# CH32V303CBT6-R0.net
KiCad netlist of a schematic drawn in Altium Designer
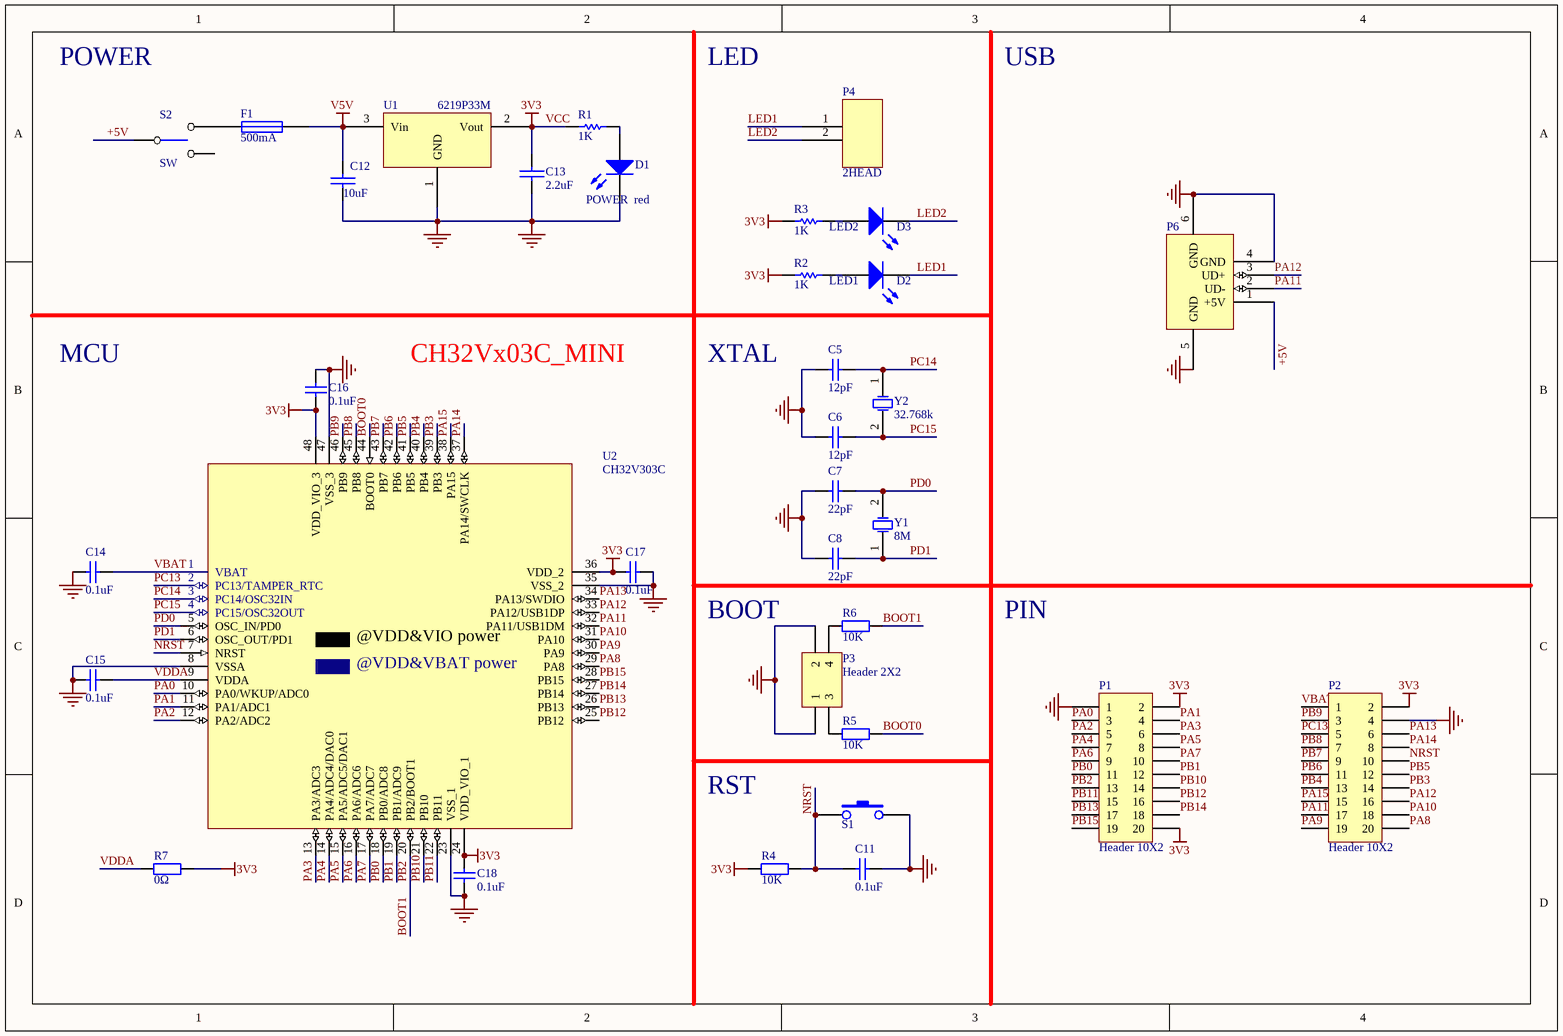
[diagram p0: CH32V303CBT6-R0.SchDoc]

(export (version "E")
  (design (tool "Eeschema 10.0.6"))
  (components
    (comp (ref "C5")
      (value "12pF")
      (footprint "0603_C")
      (description "Capacitor")
      (fields (field (name "PUBLISHER") "Altium Limited"))
      (libsource (lib "*") (part "Cap"))
    )
    (comp (ref "C6")
      (value "12pF")
      (footprint "0603_C")
      (description "Capacitor")
      (fields (field (name "PUBLISHER") "Altium Limited"))
      (libsource (lib "*") (part "Cap"))
    )
    (comp (ref "C7")
      (value "22pF")
      (footprint "0603_C")
      (description "Capacitor")
      (fields (field (name "PUBLISHER") "Altium Limited"))
      (libsource (lib "*") (part "Cap"))
    )
    (comp (ref "C8")
      (value "22pF")
      (footprint "0603_C")
      (description "Capacitor")
      (fields (field (name "PUBLISHER") "Altium Limited"))
      (libsource (lib "*") (part "Cap"))
    )
    (comp (ref "C11")
      (value "0.1uF")
      (footprint "0603_C")
      (description "Capacitor")
      (fields (field (name "PUBLISHER") "Altium Limited"))
      (libsource (lib "*") (part "Cap"))
    )
    (comp (ref "C12")
      (value "10uF")
      (footprint "3216_C")
      (description "Capacitor")
      (libsource (lib "*") (part "CAP"))
    )
    (comp (ref "C13")
      (value "2.2uF")
      (footprint "0603_C")
      (description "Capacitor")
      (libsource (lib "*") (part "CAP"))
    )
    (comp (ref "C14")
      (value "0.1uF")
      (footprint "0603_C")
      (description "Capacitor")
      (fields (field (name "PUBLISHER") "Altium Limited"))
      (libsource (lib "*") (part "Cap"))
    )
    (comp (ref "C15")
      (value "0.1uF")
      (footprint "0603_C")
      (description "Capacitor")
      (fields (field (name "PUBLISHER") "Altium Limited"))
      (libsource (lib "*") (part "Cap"))
    )
    (comp (ref "C16")
      (value "0.1uF")
      (footprint "0603_C")
      (description "Capacitor")
      (fields (field (name "PUBLISHER") "Altium Limited"))
      (libsource (lib "*") (part "Cap"))
    )
    (comp (ref "C17")
      (value "0.1uF")
      (footprint "0603_C")
      (description "Capacitor")
      (fields (field (name "PUBLISHER") "Altium Limited"))
      (libsource (lib "*") (part "Cap"))
    )
    (comp (ref "C18")
      (value "0.1uF")
      (footprint "0603_C")
      (description "Capacitor")
      (fields (field (name "PUBLISHER") "Altium Limited"))
      (libsource (lib "*") (part "Cap"))
    )
    (comp (ref "D1")
      (value "POWER  red")
      (footprint "0603+")
      (description "Typical INFRARED GaAs LED")
      (fields (field (name "PUBLISHER") "Altium Limited"))
      (libsource (lib "*") (part "LED0"))
    )
    (comp (ref "D2")
      (value "LED1")
      (footprint "0603+")
      (description "Typical INFRARED GaAs LED")
      (fields (field (name "PUBLISHER") "Altium Limited"))
      (libsource (lib "*") (part "LED0"))
    )
    (comp (ref "D3")
      (value "LED2")
      (footprint "0603+")
      (description "Typical INFRARED GaAs LED")
      (fields (field (name "PUBLISHER") "Altium Limited"))
      (libsource (lib "*") (part "LED0"))
    )
    (comp (ref "F1")
      (value "500mA")
      (footprint "0603")
      (description "Fuse")
      (libsource (lib "*") (part "FUSE1"))
    )
    (comp (ref "P1")
      (value "Header 10X2")
      (footprint "IDC20-2.54mm")
      (description "Header, 10-Pin, Dual row")
      (fields (field (name "PUBLISHER") "Altium Limited"))
      (libsource (lib "*") (part "Header 10X2"))
    )
    (comp (ref "P2")
      (value "Header 10X2")
      (footprint "IDC20-2.54mm")
      (description "Header, 10-Pin, Dual row")
      (fields (field (name "PUBLISHER") "Altium Limited"))
      (libsource (lib "*") (part "Header 10X2"))
    )
    (comp (ref "P3")
      (value "Header 2X2")
      (footprint "IDC4-2.54mm")
      (description "Header, 2-Pin, Dual row")
      (fields (field (name "PUBLISHER") "Altium Limited"))
      (libsource (lib "*") (part "Header 2X2"))
    )
    (comp (ref "P4") (value "2HEAD") (footprint "SIP2-2.54mm") (libsource (lib "*") (part "2HEAD")))
    (comp (ref "P6")
      (value "USB_A")
      (footprint "USBAF")
      (description "USB Port")
      (libsource (lib "*") (part "USB"))
    )
    (comp (ref "R1")
      (value "1K")
      (footprint "0603")
      (description "Semiconductor Resistor")
      (fields (field (name "PUBLISHER") "Altium Limited"))
      (libsource (lib "*") (part "Res Semi"))
    )
    (comp (ref "R2")
      (value "1K")
      (footprint "0603")
      (description "Semiconductor Resistor")
      (fields (field (name "PUBLISHER") "Altium Limited"))
      (libsource (lib "*") (part "Res Semi"))
    )
    (comp (ref "R3")
      (value "1K")
      (footprint "0603")
      (description "Semiconductor Resistor")
      (fields (field (name "PUBLISHER") "Altium Limited"))
      (libsource (lib "*") (part "Res Semi"))
    )
    (comp (ref "R4")
      (value "10K")
      (footprint "0603")
      (description "Resistor")
      (fields (field (name "PUBLISHER") "Altium Limited"))
      (libsource (lib "*") (part "Res2"))
    )
    (comp (ref "R5")
      (value "10K")
      (footprint "0603")
      (description "Resistor")
      (fields (field (name "PUBLISHER") "Altium Limited"))
      (libsource (lib "*") (part "Res2"))
    )
    (comp (ref "R6")
      (value "10K")
      (footprint "0603")
      (description "Resistor")
      (fields (field (name "PUBLISHER") "Altium Limited"))
      (libsource (lib "*") (part "Res2"))
    )
    (comp (ref "R7")
      (value "0Ω")
      (footprint "0603")
      (description "Resistor")
      (fields (field (name "PUBLISHER") "Altium Limited"))
      (libsource (lib "*") (part "Res2"))
    )
    (comp (ref "S1") (value "KEY") (footprint "贴片按键") (libsource (lib "*") (part "KEY")))
    (comp (ref "S2") (value "SW") (footprint "KEY2") (libsource (lib "*") (part "SW")))
    (comp (ref "U1")
      (value "6219P33M")
      (footprint "SOT-23")
      (libsource (lib "wch_sch_others") (part "6219P33M"))
    )
    (comp (ref "U2")
      (value "CH32V303C")
      (footprint "LQFP48")
      (description "RISC-V FPU HD-MCU, 144MHz, 8*UART, 10*Timer, 4*OPA")
      (libsource (lib "CHXXX") (part "CH32V303C"))
    )
    (comp (ref "Y1")
      (value "8M")
      (footprint "XT_AT49")
      (description "Crystal Oscillator")
      (fields (field (name "PUBLISHER") "Altium Limited"))
      (libsource (lib "*") (part "XTAL"))
    )
    (comp (ref "Y2")
      (value "32.768k")
      (footprint "FC-135")
      (description "Crystal Oscillator")
      (fields (field (name "PUBLISHER") "Altium Limited"))
      (libsource (lib "*") (part "XTAL"))
    )
  )
  (nets
    (net (code "1") (name "/+5V") (class "Default")
      (node (ref "P6") (pin "1") (pinfunction "+5V_1") (pintype "power_in"))
      (node (ref "S2") (pin "1") (pinfunction "1_1") (pintype "passive"))
    )
    (net (code "3") (name "/BOOT0") (class "Default")
      (node (ref "R5") (pin "1") (pinfunction "1_1") (pintype "passive"))
      (node (ref "U2") (pin "44") (pinfunction "BOOT0_44") (pintype "input"))
    )
    (net (code "4") (name "/BOOT1") (class "Default")
      (node (ref "P1") (pin "13") (pinfunction "13_13") (pintype "passive"))
      (node (ref "R6") (pin "1") (pinfunction "1_1") (pintype "passive"))
      (node (ref "U2") (pin "20") (pinfunction "PB2/BOOT1_20") (pintype "bidirectional"))
    )
    (net (code "5") (name "/LED1") (class "Default")
      (node (ref "D2") (pin "2") (pinfunction "K_2") (pintype "passive"))
      (node (ref "P4") (pin "1") (pintype "passive"))
    )
    (net (code "6") (name "/LED2") (class "Default")
      (node (ref "D3") (pin "2") (pinfunction "K_2") (pintype "passive"))
      (node (ref "P4") (pin "2") (pintype "passive"))
    )
    (net (code "7") (name "/NRST") (class "Default")
      (node (ref "C11") (pin "2") (pinfunction "2_2") (pintype "passive"))
      (node (ref "P2") (pin "10") (pinfunction "10_10") (pintype "passive"))
      (node (ref "R4") (pin "1") (pinfunction "1_1") (pintype "passive"))
      (node (ref "S1") (pin "1") (pinfunction "1_1") (pintype "passive"))
      (node (ref "U2") (pin "7") (pinfunction "NRST_7") (pintype "input"))
    )
    (net (code "8") (name "/PA0") (class "Default")
      (node (ref "P1") (pin "3") (pinfunction "3_3") (pintype "passive"))
      (node (ref "U2") (pin "10") (pinfunction "PA0/WKUP/ADC0_10") (pintype "bidirectional"))
    )
    (net (code "9") (name "/PA1") (class "Default")
      (node (ref "P1") (pin "4") (pinfunction "4_4") (pintype "passive"))
      (node (ref "U2") (pin "11") (pinfunction "PA1/ADC1_11") (pintype "bidirectional"))
    )
    (net (code "10") (name "/PA2") (class "Default")
      (node (ref "P1") (pin "5") (pinfunction "5_5") (pintype "passive"))
      (node (ref "U2") (pin "12") (pinfunction "PA2/ADC2_12") (pintype "bidirectional"))
    )
    (net (code "11") (name "/PA3") (class "Default")
      (node (ref "P1") (pin "6") (pinfunction "6_6") (pintype "passive"))
      (node (ref "U2") (pin "13") (pinfunction "PA3/ADC3_13") (pintype "bidirectional"))
    )
    (net (code "12") (name "/PA4") (class "Default")
      (node (ref "P1") (pin "7") (pinfunction "7_7") (pintype "passive"))
      (node (ref "U2") (pin "14") (pinfunction "PA4/ADC4/DAC0_14") (pintype "bidirectional"))
    )
    (net (code "13") (name "/PA5") (class "Default")
      (node (ref "P1") (pin "8") (pinfunction "8_8") (pintype "passive"))
      (node (ref "U2") (pin "15") (pinfunction "PA5/ADC5/DAC1_15") (pintype "bidirectional"))
    )
    (net (code "14") (name "/PA6") (class "Default")
      (node (ref "P1") (pin "9") (pinfunction "9_9") (pintype "passive"))
      (node (ref "U2") (pin "16") (pinfunction "PA6/ADC6_16") (pintype "bidirectional"))
    )
    (net (code "15") (name "/PA7") (class "Default")
      (node (ref "P1") (pin "10") (pinfunction "10_10") (pintype "passive"))
      (node (ref "U2") (pin "17") (pinfunction "PA7/ADC7_17") (pintype "bidirectional"))
    )
    (net (code "16") (name "/PA8") (class "Default")
      (node (ref "P2") (pin "20") (pinfunction "20_20") (pintype "passive"))
      (node (ref "U2") (pin "29") (pinfunction "PA8_29") (pintype "bidirectional"))
    )
    (net (code "17") (name "/PA9") (class "Default")
      (node (ref "P2") (pin "19") (pinfunction "19_19") (pintype "passive"))
      (node (ref "U2") (pin "30") (pinfunction "PA9_30") (pintype "bidirectional"))
    )
    (net (code "18") (name "/PA10") (class "Default")
      (node (ref "P2") (pin "18") (pinfunction "18_18") (pintype "passive"))
      (node (ref "U2") (pin "31") (pinfunction "PA10_31") (pintype "bidirectional"))
    )
    (net (code "19") (name "/PA11") (class "Default")
      (node (ref "P2") (pin "17") (pinfunction "17_17") (pintype "passive"))
      (node (ref "P6") (pin "2") (pinfunction "UD-_2") (pintype "bidirectional"))
      (node (ref "U2") (pin "32") (pinfunction "PA11/USB1DM_32") (pintype "bidirectional"))
    )
    (net (code "20") (name "/PA12") (class "Default")
      (node (ref "P2") (pin "16") (pinfunction "16_16") (pintype "passive"))
      (node (ref "P6") (pin "3") (pinfunction "UD+_3") (pintype "bidirectional"))
      (node (ref "U2") (pin "33") (pinfunction "PA12/USB1DP_33") (pintype "bidirectional"))
    )
    (net (code "21") (name "/PA13") (class "Default")
      (node (ref "P2") (pin "6") (pinfunction "6_6") (pintype "passive"))
      (node (ref "U2") (pin "34") (pinfunction "PA13/SWDIO_34") (pintype "bidirectional"))
    )
    (net (code "22") (name "/PA14") (class "Default")
      (node (ref "P2") (pin "8") (pinfunction "8_8") (pintype "passive"))
      (node (ref "U2") (pin "37") (pinfunction "PA14/SWCLK_37") (pintype "bidirectional"))
    )
    (net (code "23") (name "/PA15") (class "Default")
      (node (ref "P2") (pin "15") (pinfunction "15_15") (pintype "passive"))
      (node (ref "U2") (pin "38") (pinfunction "PA15_38") (pintype "bidirectional"))
    )
    (net (code "24") (name "/PB0") (class "Default")
      (node (ref "P1") (pin "11") (pinfunction "11_11") (pintype "passive"))
      (node (ref "U2") (pin "18") (pinfunction "PB0/ADC8_18") (pintype "bidirectional"))
    )
    (net (code "25") (name "/PB1") (class "Default")
      (node (ref "P1") (pin "12") (pinfunction "12_12") (pintype "passive"))
      (node (ref "U2") (pin "19") (pinfunction "PB1/ADC9_19") (pintype "bidirectional"))
    )
    (net (code "26") (name "/PB3") (class "Default")
      (node (ref "P2") (pin "14") (pinfunction "14_14") (pintype "passive"))
      (node (ref "U2") (pin "39") (pinfunction "PB3_39") (pintype "bidirectional"))
    )
    (net (code "27") (name "/PB4") (class "Default")
      (node (ref "P2") (pin "13") (pinfunction "13_13") (pintype "passive"))
      (node (ref "U2") (pin "40") (pinfunction "PB4_40") (pintype "bidirectional"))
    )
    (net (code "28") (name "/PB5") (class "Default")
      (node (ref "P2") (pin "12") (pinfunction "12_12") (pintype "passive"))
      (node (ref "U2") (pin "41") (pinfunction "PB5_41") (pintype "bidirectional"))
    )
    (net (code "29") (name "/PB6") (class "Default")
      (node (ref "P2") (pin "11") (pinfunction "11_11") (pintype "passive"))
      (node (ref "U2") (pin "42") (pinfunction "PB6_42") (pintype "bidirectional"))
    )
    (net (code "30") (name "/PB7") (class "Default")
      (node (ref "P2") (pin "9") (pinfunction "9_9") (pintype "passive"))
      (node (ref "U2") (pin "43") (pinfunction "PB7_43") (pintype "bidirectional"))
    )
    (net (code "31") (name "/PB8") (class "Default")
      (node (ref "P2") (pin "7") (pinfunction "7_7") (pintype "passive"))
      (node (ref "U2") (pin "45") (pinfunction "PB8_45") (pintype "bidirectional"))
    )
    (net (code "32") (name "/PB9") (class "Default")
      (node (ref "P2") (pin "3") (pinfunction "3_3") (pintype "passive"))
      (node (ref "U2") (pin "46") (pinfunction "PB9_46") (pintype "bidirectional"))
    )
    (net (code "33") (name "/PB10") (class "Default")
      (node (ref "P1") (pin "14") (pinfunction "14_14") (pintype "passive"))
      (node (ref "U2") (pin "21") (pinfunction "PB10_21") (pintype "bidirectional"))
    )
    (net (code "34") (name "/PB11") (class "Default")
      (node (ref "P1") (pin "15") (pinfunction "15_15") (pintype "passive"))
      (node (ref "U2") (pin "22") (pinfunction "PB11_22") (pintype "bidirectional"))
    )
    (net (code "35") (name "/PB12") (class "Default")
      (node (ref "P1") (pin "16") (pinfunction "16_16") (pintype "passive"))
      (node (ref "U2") (pin "25") (pinfunction "PB12_25") (pintype "bidirectional"))
    )
    (net (code "36") (name "/PB13") (class "Default")
      (node (ref "P1") (pin "17") (pinfunction "17_17") (pintype "passive"))
      (node (ref "U2") (pin "26") (pinfunction "PB13_26") (pintype "bidirectional"))
    )
    (net (code "37") (name "/PB14") (class "Default")
      (node (ref "P1") (pin "18") (pinfunction "18_18") (pintype "passive"))
      (node (ref "U2") (pin "27") (pinfunction "PB14_27") (pintype "bidirectional"))
    )
    (net (code "38") (name "/PB15") (class "Default")
      (node (ref "P1") (pin "19") (pinfunction "19_19") (pintype "passive"))
      (node (ref "U2") (pin "28") (pinfunction "PB15_28") (pintype "bidirectional"))
    )
    (net (code "39") (name "/PC13") (class "Default")
      (node (ref "P2") (pin "5") (pinfunction "5_5") (pintype "passive"))
      (node (ref "U2") (pin "2") (pinfunction "PC13/TAMPER_RTC_2") (pintype "bidirectional"))
    )
    (net (code "40") (name "/PC14") (class "Default")
      (node (ref "C5") (pin "1") (pinfunction "1_1") (pintype "passive"))
      (node (ref "U2") (pin "3") (pinfunction "PC14/OSC32IN_3") (pintype "bidirectional"))
      (node (ref "Y2") (pin "1") (pinfunction "OSC1_1") (pintype "passive"))
    )
    (net (code "41") (name "/PC15") (class "Default")
      (node (ref "C6") (pin "1") (pinfunction "1_1") (pintype "passive"))
      (node (ref "U2") (pin "4") (pinfunction "PC15/OSC32OUT_4") (pintype "bidirectional"))
      (node (ref "Y2") (pin "2") (pinfunction "OSC2_2") (pintype "passive"))
    )
    (net (code "42") (name "/PD0") (class "Default")
      (node (ref "C7") (pin "2") (pinfunction "2_2") (pintype "passive"))
      (node (ref "U2") (pin "5") (pinfunction "OSC_IN/PD0_5") (pintype "bidirectional"))
      (node (ref "Y1") (pin "2") (pinfunction "OSC2_2") (pintype "passive"))
    )
    (net (code "43") (name "/PD1") (class "Default")
      (node (ref "C8") (pin "2") (pinfunction "2_2") (pintype "passive"))
      (node (ref "U2") (pin "6") (pinfunction "OSC_OUT/PD1_6") (pintype "bidirectional"))
      (node (ref "Y1") (pin "1") (pinfunction "OSC1_1") (pintype "passive"))
    )
    (net (code "44") (name "/VBAT") (class "Default")
      (node (ref "C14") (pin "1") (pinfunction "1_1") (pintype "passive"))
      (node (ref "P2") (pin "1") (pinfunction "1_1") (pintype "passive"))
      (node (ref "U2") (pin "1") (pinfunction "VBAT_1") (pintype "power_in"))
    )
    (net (code "45") (name "/VDDA") (class "Default")
      (node (ref "C15") (pin "1") (pinfunction "1_1") (pintype "passive"))
      (node (ref "R7") (pin "2") (pinfunction "2_2") (pintype "passive"))
      (node (ref "U2") (pin "9") (pinfunction "VDDA_9") (pintype "power_in"))
    )
    (net (code "46") (name "3V3") (class "Default")
      (node (ref "C13") (pin "1") (pinfunction "1_1") (pintype "passive"))
      (node (ref "C16") (pin "2") (pinfunction "2_2") (pintype "passive"))
      (node (ref "C17") (pin "2") (pinfunction "2_2") (pintype "passive"))
      (node (ref "C18") (pin "2") (pinfunction "2_2") (pintype "passive"))
      (node (ref "P1") (pin "2") (pinfunction "2_2") (pintype "passive"))
      (node (ref "P1") (pin "20") (pinfunction "20_20") (pintype "passive"))
      (node (ref "P2") (pin "2") (pinfunction "2_2") (pintype "passive"))
      (node (ref "R1") (pin "2") (pinfunction "2_2") (pintype "passive"))
      (node (ref "R2") (pin "1") (pinfunction "1_1") (pintype "passive"))
      (node (ref "R3") (pin "1") (pinfunction "1_1") (pintype "passive"))
      (node (ref "R4") (pin "2") (pinfunction "2_2") (pintype "passive"))
      (node (ref "R7") (pin "1") (pinfunction "1_1") (pintype "passive"))
      (node (ref "U1") (pin "2") (pinfunction "Vout_2") (pintype "passive"))
      (node (ref "U2") (pin "24") (pinfunction "VDD_VIO_1_24") (pintype "power_in"))
      (node (ref "U2") (pin "36") (pinfunction "VDD_2_36") (pintype "power_in"))
      (node (ref "U2") (pin "48") (pinfunction "VDD_VIO_3_48") (pintype "power_in"))
    )
    (net (code "47") (name "GND") (class "Default")
      (node (ref "C11") (pin "1") (pinfunction "1_1") (pintype "passive"))
      (node (ref "C12") (pin "2") (pinfunction "2_2") (pintype "passive"))
      (node (ref "C13") (pin "2") (pinfunction "2_2") (pintype "passive"))
      (node (ref "C14") (pin "2") (pinfunction "2_2") (pintype "passive"))
      (node (ref "C15") (pin "2") (pinfunction "2_2") (pintype "passive"))
      (node (ref "C16") (pin "1") (pinfunction "1_1") (pintype "passive"))
      (node (ref "C17") (pin "1") (pinfunction "1_1") (pintype "passive"))
      (node (ref "C18") (pin "1") (pinfunction "1_1") (pintype "passive"))
      (node (ref "C5") (pin "2") (pinfunction "2_2") (pintype "passive"))
      (node (ref "C6") (pin "2") (pinfunction "2_2") (pintype "passive"))
      (node (ref "C7") (pin "1") (pinfunction "1_1") (pintype "passive"))
      (node (ref "C8") (pin "1") (pinfunction "1_1") (pintype "passive"))
      (node (ref "D1") (pin "2") (pinfunction "K_2") (pintype "passive"))
      (node (ref "P1") (pin "1") (pinfunction "1_1") (pintype "passive"))
      (node (ref "P2") (pin "4") (pinfunction "4_4") (pintype "passive"))
      (node (ref "P3") (pin "1") (pinfunction "1_1") (pintype "passive"))
      (node (ref "P3") (pin "2") (pinfunction "2_2") (pintype "passive"))
      (node (ref "P6") (pin "4") (pinfunction "GND_4") (pintype "power_in"))
      (node (ref "P6") (pin "5") (pinfunction "GND_5") (pintype "power_in"))
      (node (ref "P6") (pin "6") (pinfunction "GND_6") (pintype "power_in"))
      (node (ref "S1") (pin "2") (pinfunction "2_2") (pintype "passive"))
      (node (ref "U1") (pin "1") (pinfunction "GND_1") (pintype "passive"))
      (node (ref "U2") (pin "23") (pinfunction "VSS_1_23") (pintype "power_in"))
      (node (ref "U2") (pin "35") (pinfunction "VSS_2_35") (pintype "power_in"))
      (node (ref "U2") (pin "47") (pinfunction "VSS_3_47") (pintype "power_in"))
      (node (ref "U2") (pin "8") (pinfunction "VSSA_8") (pintype "power_in"))
    )
    (net (code "48") (name "Net-(D1-A)") (class "Default")
      (node (ref "D1") (pin "1") (pinfunction "A_1") (pintype "passive"))
      (node (ref "R1") (pin "1") (pinfunction "1_1") (pintype "passive"))
    )
    (net (code "49") (name "Net-(D2-A)") (class "Default")
      (node (ref "D2") (pin "1") (pinfunction "A_1") (pintype "passive"))
      (node (ref "R2") (pin "2") (pinfunction "2_2") (pintype "passive"))
    )
    (net (code "50") (name "Net-(D3-A)") (class "Default")
      (node (ref "D3") (pin "1") (pinfunction "A_1") (pintype "passive"))
      (node (ref "R3") (pin "2") (pinfunction "2_2") (pintype "passive"))
    )
    (net (code "51") (name "Net-(F1-Pad1)") (class "Default")
      (node (ref "F1") (pin "1") (pinfunction "1_1") (pintype "passive"))
      (node (ref "S2") (pin "3") (pinfunction "3_3") (pintype "passive"))
    )
    (net (code "52") (name "Net-(P3-Pad3)") (class "Default")
      (node (ref "P3") (pin "3") (pinfunction "3_3") (pintype "passive"))
      (node (ref "R5") (pin "2") (pinfunction "2_2") (pintype "passive"))
    )
    (net (code "53") (name "Net-(P3-Pad4)") (class "Default")
      (node (ref "P3") (pin "4") (pinfunction "4_4") (pintype "passive"))
      (node (ref "R6") (pin "2") (pinfunction "2_2") (pintype "passive"))
    )
    (net (code "54") (name "V5V") (class "Default")
      (node (ref "C12") (pin "1") (pinfunction "1_1") (pintype "passive"))
      (node (ref "F1") (pin "2") (pinfunction "2_2") (pintype "passive"))
      (node (ref "U1") (pin "3") (pinfunction "Vin_3") (pintype "passive"))
    )
    (net (code "55") (name "unconnected-(S2-Pad2)") (class "Default")
      (node (ref "S2") (pin "2") (pinfunction "2_2") (pintype "passive"))
    )
  )
)
